# pc_healthypi_pro_carrier_5_2.net
KiCad netlist of a schematic drawn in EAGLE
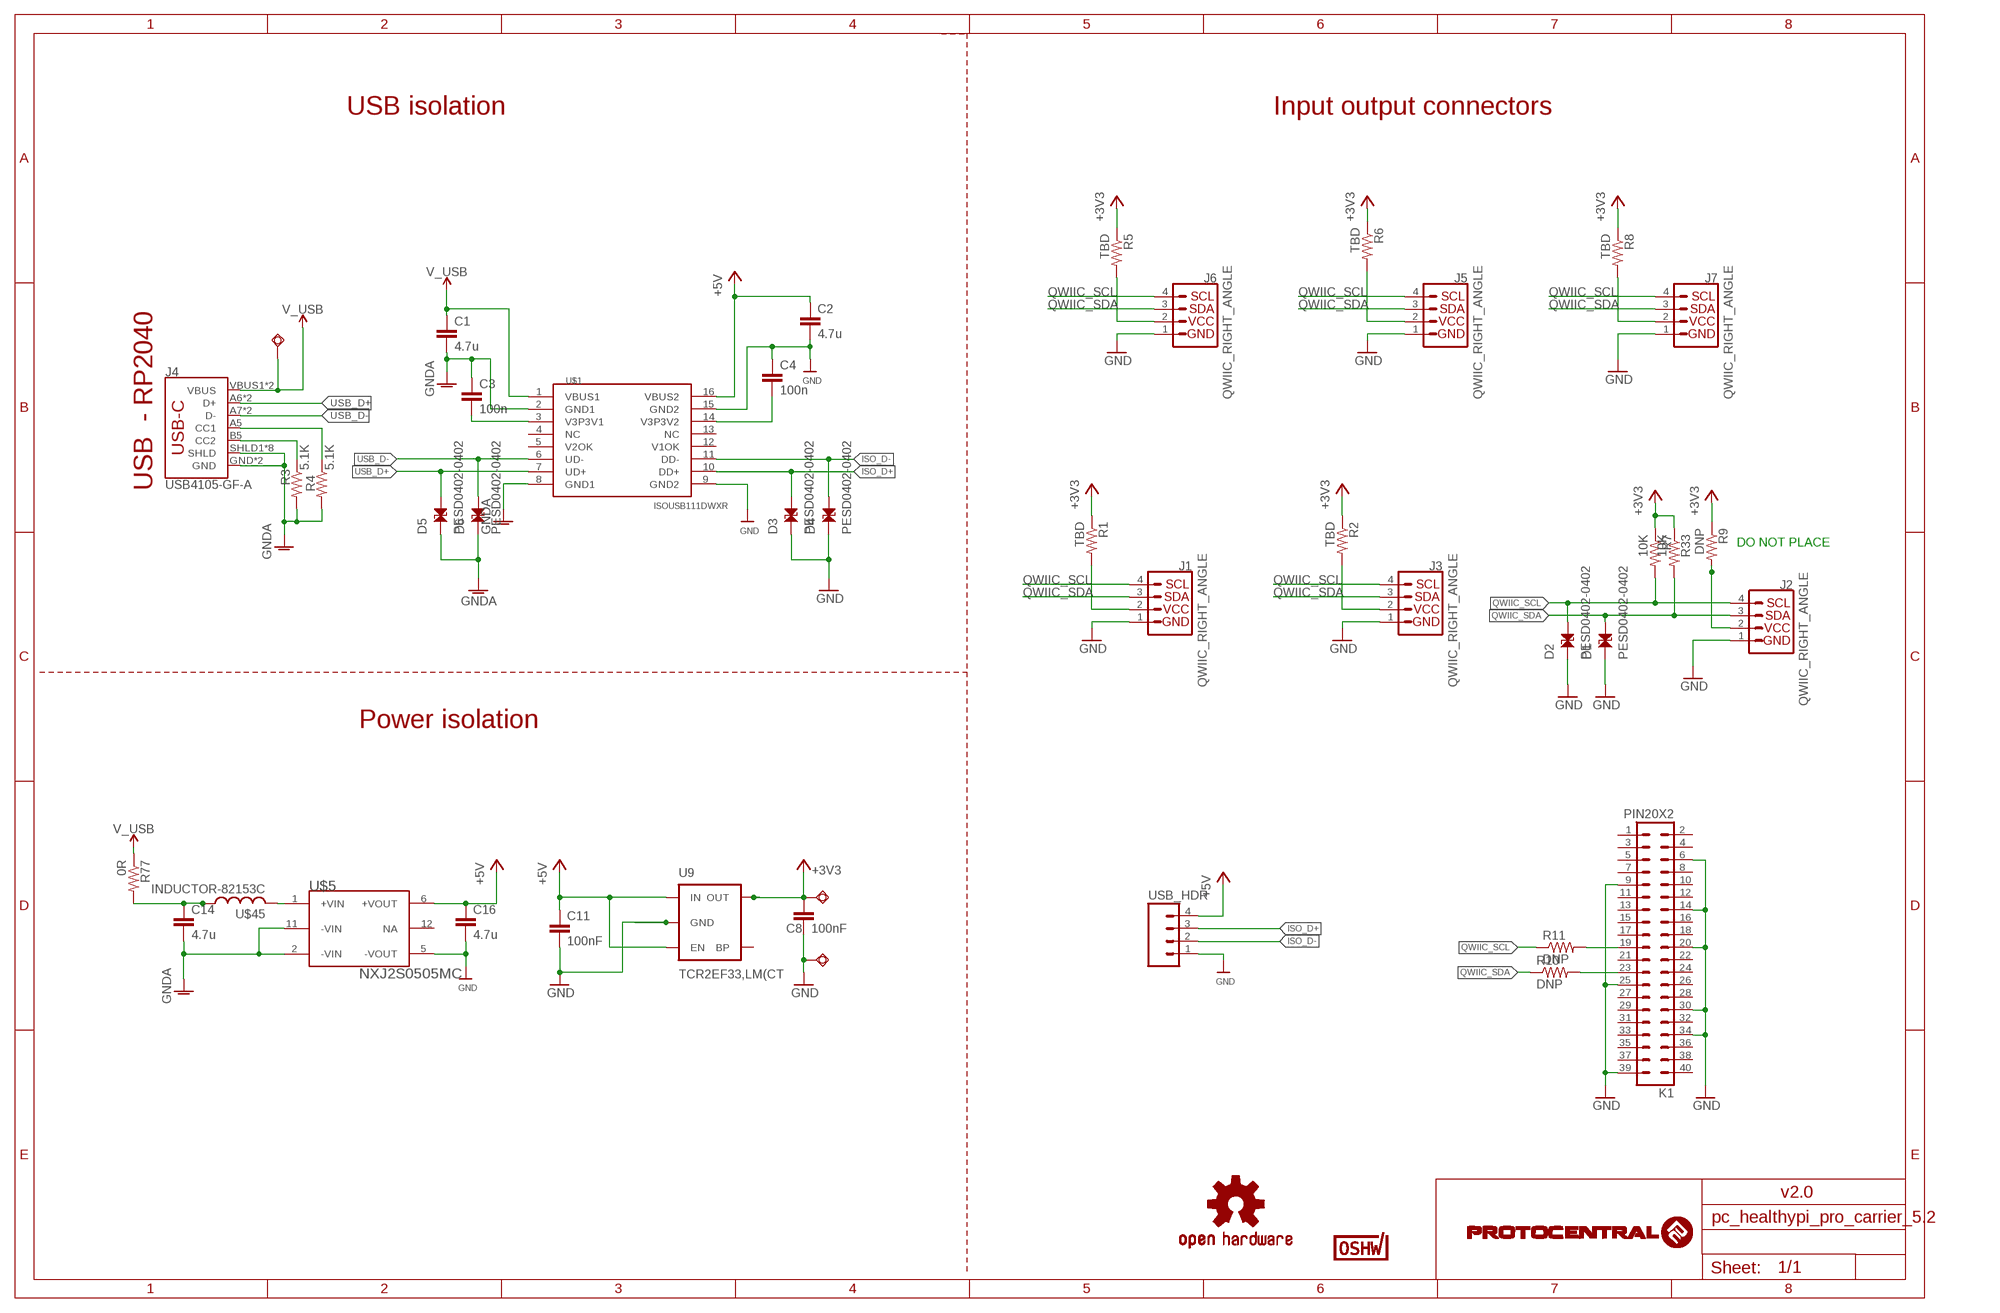
[diagram p0: schematic, sheet 1]

(export (version "E")
  (design (tool "Eeschema 10.0.6"))
  (components
    (comp (ref "C1")
      (value "4.7u")
      (footprint "eagle-import:C0805")
      (libsource (lib "eagle-import") (part "C-EUC0805"))
    )
    (comp (ref "C2")
      (value "4.7u")
      (footprint "eagle-import:C0805")
      (libsource (lib "eagle-import") (part "C-EUC0805"))
    )
    (comp (ref "C3")
      (value "100n")
      (footprint "eagle-import:C0402")
      (libsource (lib "eagle-import") (part "C-EUC0402"))
    )
    (comp (ref "C4")
      (value "100n")
      (footprint "eagle-import:C0402")
      (libsource (lib "eagle-import") (part "C-EUC0402"))
    )
    (comp (ref "C8")
      (value "100nF")
      (footprint "eagle-import:C0402")
      (libsource (lib "eagle-import") (part "C-EUC0402"))
    )
    (comp (ref "C11")
      (value "100nF")
      (footprint "eagle-import:C0402")
      (libsource (lib "eagle-import") (part "C-EUC0402"))
    )
    (comp (ref "C14")
      (value "4.7u")
      (footprint "eagle-import:C0805")
      (libsource (lib "eagle-import") (part "C-EUC0805"))
    )
    (comp (ref "C16")
      (value "4.7u")
      (footprint "eagle-import:C0805")
      (libsource (lib "eagle-import") (part "C-EUC0805"))
    )
    (comp (ref "D1")
      (value "PESD0402-0402")
      (footprint "eagle-import:0402")
      (fields
        (field (name "DIGIKEY_PART") "PESD0402-140CT-ND")
        (field (name "MOUSE_PART") "650-PESD0402-140")
      )
      (libsource (lib "eagle-import") (part "PESD0402-0402"))
    )
    (comp (ref "D2")
      (value "PESD0402-0402")
      (footprint "eagle-import:0402")
      (fields
        (field (name "DIGIKEY_PART") "PESD0402-140CT-ND")
        (field (name "MOUSE_PART") "650-PESD0402-140")
      )
      (libsource (lib "eagle-import") (part "PESD0402-0402"))
    )
    (comp (ref "D3")
      (value "PESD0402-0402")
      (footprint "eagle-import:0402")
      (fields
        (field (name "DIGIKEY_PART") "PESD0402-140CT-ND")
        (field (name "MOUSE_PART") "650-PESD0402-140")
      )
      (libsource (lib "eagle-import") (part "PESD0402-0402"))
    )
    (comp (ref "D4")
      (value "PESD0402-0402")
      (footprint "eagle-import:0402")
      (fields
        (field (name "DIGIKEY_PART") "PESD0402-140CT-ND")
        (field (name "MOUSE_PART") "650-PESD0402-140")
      )
      (libsource (lib "eagle-import") (part "PESD0402-0402"))
    )
    (comp (ref "D5")
      (value "PESD0402-0402")
      (footprint "eagle-import:0402")
      (fields
        (field (name "DIGIKEY_PART") "PESD0402-140CT-ND")
        (field (name "MOUSE_PART") "650-PESD0402-140")
      )
      (libsource (lib "eagle-import") (part "PESD0402-0402"))
    )
    (comp (ref "D6")
      (value "PESD0402-0402")
      (footprint "eagle-import:0402")
      (fields
        (field (name "DIGIKEY_PART") "PESD0402-140CT-ND")
        (field (name "MOUSE_PART") "650-PESD0402-140")
      )
      (libsource (lib "eagle-import") (part "PESD0402-0402"))
    )
    (comp (ref "J1")
      (value "QWIIC_RIGHT_ANGLE")
      (footprint "eagle-import:JST04_1MM_RA")
      (libsource (lib "eagle-import") (part "QWIIC_CONNECTORJS-1MM"))
    )
    (comp (ref "J2")
      (value "QWIIC_RIGHT_ANGLE")
      (footprint "eagle-import:JST04_1MM_RA")
      (libsource (lib "eagle-import") (part "QWIIC_CONNECTORJS-1MM"))
    )
    (comp (ref "J3")
      (value "QWIIC_RIGHT_ANGLE")
      (footprint "eagle-import:JST04_1MM_RA")
      (libsource (lib "eagle-import") (part "QWIIC_CONNECTORJS-1MM"))
    )
    (comp (ref "J4")
      (value "USB4105-GF-A")
      (footprint "eagle-import:USB-C-16P")
      (libsource (lib "eagle-import") (part "USB_C16PIN"))
    )
    (comp (ref "J5")
      (value "QWIIC_RIGHT_ANGLE")
      (footprint "eagle-import:JST04_1MM_RA")
      (libsource (lib "eagle-import") (part "QWIIC_CONNECTORJS-1MM"))
    )
    (comp (ref "J6")
      (value "QWIIC_RIGHT_ANGLE")
      (footprint "eagle-import:JST04_1MM_RA")
      (libsource (lib "eagle-import") (part "QWIIC_CONNECTORJS-1MM"))
    )
    (comp (ref "J7")
      (value "QWIIC_RIGHT_ANGLE")
      (footprint "eagle-import:JST04_1MM_RA")
      (libsource (lib "eagle-import") (part "QWIIC_CONNECTORJS-1MM"))
    )
    (comp (ref "K1")
      (value "PIN20X2")
      (footprint "eagle-import:PIN_20X2")
      (libsource (lib "eagle-import") (part "PIN20X2"))
    )
    (comp (ref "R1")
      (value "TBD")
      (footprint "eagle-import:R0402")
      (libsource (lib "eagle-import") (part "rcl_334_R-US_R0402"))
    )
    (comp (ref "R2")
      (value "TBD")
      (footprint "eagle-import:R0402")
      (libsource (lib "eagle-import") (part "rcl_334_R-US_R0402"))
    )
    (comp (ref "R3")
      (value "5.1K")
      (footprint "eagle-import:R0402")
      (libsource (lib "eagle-import") (part "rcl_334_R-US_R0402"))
    )
    (comp (ref "R4")
      (value "5.1K")
      (footprint "eagle-import:R0402")
      (libsource (lib "eagle-import") (part "rcl_334_R-US_R0402"))
    )
    (comp (ref "R5")
      (value "TBD")
      (footprint "eagle-import:R0402")
      (libsource (lib "eagle-import") (part "rcl_334_R-US_R0402"))
    )
    (comp (ref "R6")
      (value "TBD")
      (footprint "eagle-import:R0402")
      (libsource (lib "eagle-import") (part "rcl_334_R-US_R0402"))
    )
    (comp (ref "R7")
      (value "10K")
      (footprint "eagle-import:R0402")
      (libsource (lib "eagle-import") (part "rcl_334_R-US_R0402"))
    )
    (comp (ref "R8")
      (value "TBD")
      (footprint "eagle-import:R0402")
      (libsource (lib "eagle-import") (part "rcl_334_R-US_R0402"))
    )
    (comp (ref "R9")
      (value "DNP")
      (footprint "eagle-import:R0402")
      (libsource (lib "eagle-import") (part "rcl_334_R-US_R0402"))
    )
    (comp (ref "R10")
      (value "DNP")
      (footprint "eagle-import:R0402")
      (libsource (lib "eagle-import") (part "rcl_334_R-US_R0402"))
    )
    (comp (ref "R11")
      (value "DNP")
      (footprint "eagle-import:R0402")
      (libsource (lib "eagle-import") (part "rcl_334_R-US_R0402"))
    )
    (comp (ref "R33")
      (value "10K")
      (footprint "eagle-import:R0402")
      (libsource (lib "eagle-import") (part "rcl_334_R-US_R0402"))
    )
    (comp (ref "R77")
      (value "0R")
      (footprint "eagle-import:R0805")
      (libsource (lib "eagle-import") (part "R-US_R0805"))
    )
    (comp (ref "SWIO5")
      (value "TPSQTP11R")
      (footprint "eagle-import:TP11R")
      (libsource (lib "eagle-import") (part "TPSQTP11R"))
    )
    (comp (ref "SWIO6")
      (value "TPSQTP11R")
      (footprint "eagle-import:TP11R")
      (libsource (lib "eagle-import") (part "TPSQTP11R"))
    )
    (comp (ref "TP8")
      (value "TPSQTP11R")
      (footprint "eagle-import:TP11R")
      (libsource (lib "eagle-import") (part "TPSQTP11R"))
    )
    (comp (ref "U$1")
      (value "ISOUSB111DWXR")
      (footprint "eagle-import:SSOP-16-5.85X7.5")
      (libsource (lib "eagle-import") (part "ISOUSB111DWXR"))
    )
    (comp (ref "U$5")
      (value "NXJ2S0505MC")
      (footprint "eagle-import:NXJ2S0505MC")
      (libsource (lib "eagle-import") (part "NXJ2S0505MC"))
    )
    (comp (ref "U$13")
      (value "CERT-SMALL")
      (footprint "eagle-import:CERT-SMALL-SILK")
      (libsource (lib "eagle-import") (part "CERT-SMALL"))
    )
    (comp (ref "U$42")
      (value "OSHW-LOGOM")
      (footprint "eagle-import:OSHW-LOGO-M")
      (libsource (lib "eagle-import") (part "OSHW-LOGOM"))
    )
    (comp (ref "U$45")
      (value "INDUCTOR-82153C")
      (footprint "eagle-import:INDUCTOR-8200")
      (libsource (lib "eagle-import") (part "INDUCTOR-82153C"))
    )
    (comp (ref "U9")
      (value "TCR2EF33,LM(CT")
      (footprint "eagle-import:SOT23-5")
      (libsource (lib "eagle-import") (part "V_REG_LDOSMD"))
    )
    (comp (ref "USB_HDR")
      (value "M04LOCK_LONGPADS")
      (footprint "eagle-import:1X04_LOCK_LONGPADS")
      (libsource (lib "eagle-import") (part "M04LOCK_LONGPADS"))
    )
  )
  (nets
    (net (code "1") (name "+3V3") (class "Default")
      (node (ref "C8") (pin "1") (pinfunction "1_1") (pintype "passive"))
      (node (ref "R1") (pin "1") (pinfunction "1_1") (pintype "passive"))
      (node (ref "R2") (pin "1") (pinfunction "1_1") (pintype "passive"))
      (node (ref "R33") (pin "1") (pinfunction "1_1") (pintype "passive"))
      (node (ref "R5") (pin "1") (pinfunction "1_1") (pintype "passive"))
      (node (ref "R6") (pin "1") (pinfunction "1_1") (pintype "passive"))
      (node (ref "R7") (pin "1") (pinfunction "1_1") (pintype "passive"))
      (node (ref "R8") (pin "1") (pinfunction "1_1") (pintype "passive"))
      (node (ref "R9") (pin "1") (pinfunction "1_1") (pintype "passive"))
      (node (ref "SWIO5") (pin "TP") (pinfunction "TP_TP") (pintype "input"))
      (node (ref "U9") (pin "5") (pinfunction "OUT_5") (pintype "passive"))
    )
    (net (code "2") (name "+5V") (class "Default")
      (node (ref "C11") (pin "1") (pinfunction "1_1") (pintype "passive"))
      (node (ref "C16") (pin "1") (pinfunction "1_1") (pintype "passive"))
      (node (ref "C2") (pin "1") (pinfunction "1_1") (pintype "passive"))
      (node (ref "U$1") (pin "16") (pinfunction "VBUS2_16") (pintype "bidirectional"))
      (node (ref "U$5") (pin "6") (pinfunction "+VOUT_6") (pintype "bidirectional"))
      (node (ref "U9") (pin "1") (pinfunction "IN_1") (pintype "input"))
      (node (ref "U9") (pin "3") (pinfunction "EN_3") (pintype "input"))
      (node (ref "USB_HDR") (pin "4") (pinfunction "4_4") (pintype "passive"))
    )
    (net (code "3") (name "GND") (class "Default")
      (node (ref "C11") (pin "2") (pinfunction "2_2") (pintype "passive"))
      (node (ref "C16") (pin "2") (pinfunction "2_2") (pintype "passive"))
      (node (ref "C2") (pin "2") (pinfunction "2_2") (pintype "passive"))
      (node (ref "C4") (pin "1") (pinfunction "1_1") (pintype "passive"))
      (node (ref "C8") (pin "2") (pinfunction "2_2") (pintype "passive"))
      (node (ref "D1") (pin "1") (pinfunction "1_1") (pintype "bidirectional"))
      (node (ref "D2") (pin "1") (pinfunction "1_1") (pintype "bidirectional"))
      (node (ref "D3") (pin "1") (pinfunction "1_1") (pintype "bidirectional"))
      (node (ref "D4") (pin "1") (pinfunction "1_1") (pintype "bidirectional"))
      (node (ref "J1") (pin "1") (pinfunction "1_1") (pintype "power_in"))
      (node (ref "J2") (pin "1") (pinfunction "1_1") (pintype "power_in"))
      (node (ref "J3") (pin "1") (pinfunction "1_1") (pintype "power_in"))
      (node (ref "J5") (pin "1") (pinfunction "1_1") (pintype "power_in"))
      (node (ref "J6") (pin "1") (pinfunction "1_1") (pintype "power_in"))
      (node (ref "J7") (pin "1") (pinfunction "1_1") (pintype "power_in"))
      (node (ref "K1") (pin "14") (pinfunction "14_14") (pintype "passive"))
      (node (ref "K1") (pin "20") (pinfunction "20_20") (pintype "passive"))
      (node (ref "K1") (pin "25") (pinfunction "25_25") (pintype "passive"))
      (node (ref "K1") (pin "30") (pinfunction "30_30") (pintype "passive"))
      (node (ref "K1") (pin "34") (pinfunction "34_34") (pintype "passive"))
      (node (ref "K1") (pin "39") (pinfunction "39_39") (pintype "passive"))
      (node (ref "K1") (pin "6") (pinfunction "6_6") (pintype "passive"))
      (node (ref "K1") (pin "9") (pinfunction "9_9") (pintype "passive"))
      (node (ref "SWIO6") (pin "TP") (pinfunction "TP_TP") (pintype "input"))
      (node (ref "U$1") (pin "15") (pinfunction "GND2_15") (pintype "bidirectional"))
      (node (ref "U$1") (pin "9") (pinfunction "GND2_9") (pintype "bidirectional"))
      (node (ref "U$5") (pin "5") (pinfunction "-VOUT_5") (pintype "bidirectional"))
      (node (ref "U9") (pin "2") (pinfunction "GND_2") (pintype "input"))
      (node (ref "USB_HDR") (pin "1") (pinfunction "1_1") (pintype "passive"))
    )
    (net (code "4") (name "GNDA") (class "Default")
      (node (ref "C1") (pin "2") (pinfunction "2_2") (pintype "passive"))
      (node (ref "C14") (pin "2") (pinfunction "2_2") (pintype "passive"))
      (node (ref "C3") (pin "1") (pinfunction "1_1") (pintype "passive"))
      (node (ref "D5") (pin "1") (pinfunction "1_1") (pintype "bidirectional"))
      (node (ref "D6") (pin "1") (pinfunction "1_1") (pintype "bidirectional"))
      (node (ref "J4") (pin "GND") (pinfunction "GND_GND") (pintype "bidirectional"))
      (node (ref "J4") (pin "GND2") (pinfunction "GND_GND2") (pintype "bidirectional"))
      (node (ref "J4") (pin "SHLD1") (pinfunction "SHLD_SHLD1") (pintype "bidirectional"))
      (node (ref "J4") (pin "SHLD2") (pinfunction "SHLD_SHLD2") (pintype "bidirectional"))
      (node (ref "J4") (pin "SHLD3") (pinfunction "SHLD_SHLD3") (pintype "bidirectional"))
      (node (ref "J4") (pin "SHLD4") (pinfunction "SHLD_SHLD4") (pintype "bidirectional"))
      (node (ref "J4") (pin "SHLD5") (pinfunction "SHLD_SHLD5") (pintype "bidirectional"))
      (node (ref "J4") (pin "SHLD6") (pinfunction "SHLD_SHLD6") (pintype "bidirectional"))
      (node (ref "J4") (pin "SHLD7") (pinfunction "SHLD_SHLD7") (pintype "bidirectional"))
      (node (ref "J4") (pin "SHLD8") (pinfunction "SHLD_SHLD8") (pintype "bidirectional"))
      (node (ref "R3") (pin "2") (pinfunction "2_2") (pintype "passive"))
      (node (ref "R4") (pin "2") (pinfunction "2_2") (pintype "passive"))
      (node (ref "U$1") (pin "2") (pinfunction "GND1_2") (pintype "bidirectional"))
      (node (ref "U$1") (pin "8") (pinfunction "GND1_8") (pintype "bidirectional"))
      (node (ref "U$5") (pin "11") (pinfunction "-VIN_11") (pintype "bidirectional"))
      (node (ref "U$5") (pin "2") (pinfunction "-VIN_2") (pintype "bidirectional"))
    )
    (net (code "5") (name "ISO_D+") (class "Default")
      (node (ref "D3") (pin "2") (pinfunction "2_2") (pintype "bidirectional"))
      (node (ref "U$1") (pin "10") (pinfunction "DD+_10") (pintype "bidirectional"))
      (node (ref "USB_HDR") (pin "3") (pinfunction "3_3") (pintype "passive"))
    )
    (net (code "6") (name "ISO_D-") (class "Default")
      (node (ref "D4") (pin "2") (pinfunction "2_2") (pintype "bidirectional"))
      (node (ref "U$1") (pin "11") (pinfunction "DD-_11") (pintype "bidirectional"))
      (node (ref "USB_HDR") (pin "2") (pinfunction "2_2") (pintype "passive"))
    )
    (net (code "7") (name "Net-(J1-Pad2)") (class "Default")
      (node (ref "J1") (pin "2") (pinfunction "2_2") (pintype "power_in"))
      (node (ref "R1") (pin "2") (pinfunction "2_2") (pintype "passive"))
    )
    (net (code "8") (name "Net-(J2-Pad2)") (class "Default")
      (node (ref "J2") (pin "2") (pinfunction "2_2") (pintype "power_in"))
      (node (ref "R9") (pin "2") (pinfunction "2_2") (pintype "passive"))
    )
    (net (code "9") (name "Net-(J3-Pad2)") (class "Default")
      (node (ref "J3") (pin "2") (pinfunction "2_2") (pintype "power_in"))
      (node (ref "R2") (pin "2") (pinfunction "2_2") (pintype "passive"))
    )
    (net (code "10") (name "Net-(J4-CC1)") (class "Default")
      (node (ref "J4") (pin "A5") (pinfunction "CC1_A5") (pintype "bidirectional"))
      (node (ref "R4") (pin "1") (pinfunction "1_1") (pintype "passive"))
    )
    (net (code "11") (name "Net-(J4-CC2)") (class "Default")
      (node (ref "J4") (pin "B5") (pinfunction "CC2_B5") (pintype "bidirectional"))
      (node (ref "R3") (pin "1") (pinfunction "1_1") (pintype "passive"))
    )
    (net (code "12") (name "Net-(J5-Pad2)") (class "Default")
      (node (ref "J5") (pin "2") (pinfunction "2_2") (pintype "power_in"))
      (node (ref "R6") (pin "2") (pinfunction "2_2") (pintype "passive"))
    )
    (net (code "13") (name "Net-(J6-Pad2)") (class "Default")
      (node (ref "J6") (pin "2") (pinfunction "2_2") (pintype "power_in"))
      (node (ref "R5") (pin "2") (pinfunction "2_2") (pintype "passive"))
    )
    (net (code "14") (name "Net-(J7-Pad2)") (class "Default")
      (node (ref "J7") (pin "2") (pinfunction "2_2") (pintype "power_in"))
      (node (ref "R8") (pin "2") (pinfunction "2_2") (pintype "passive"))
    )
    (net (code "15") (name "Net-(K1-Pad19)") (class "Default")
      (node (ref "K1") (pin "19") (pinfunction "19_19") (pintype "passive"))
      (node (ref "R11") (pin "2") (pinfunction "2_2") (pintype "passive"))
    )
    (net (code "16") (name "Net-(K1-Pad23)") (class "Default")
      (node (ref "K1") (pin "23") (pinfunction "23_23") (pintype "passive"))
      (node (ref "R10") (pin "2") (pinfunction "2_2") (pintype "passive"))
    )
    (net (code "17") (name "Net-(U$1-V3P3V1)") (class "Default")
      (node (ref "C3") (pin "2") (pinfunction "2_2") (pintype "passive"))
      (node (ref "U$1") (pin "3") (pinfunction "V3P3V1_3") (pintype "bidirectional"))
    )
    (net (code "18") (name "Net-(U$1-V3P3V2)") (class "Default")
      (node (ref "C4") (pin "2") (pinfunction "2_2") (pintype "passive"))
      (node (ref "U$1") (pin "14") (pinfunction "V3P3V2_14") (pintype "bidirectional"))
    )
    (net (code "19") (name "Net-(U$45-1)") (class "Default")
      (node (ref "C14") (pin "1") (pinfunction "1_1") (pintype "passive"))
      (node (ref "R77") (pin "2") (pinfunction "2_2") (pintype "passive"))
      (node (ref "U$45") (pin "P$1") (pinfunction "1_P$1") (pintype "passive"))
    )
    (net (code "20") (name "Net-(U$45-2)") (class "Default")
      (node (ref "U$45") (pin "P$2") (pinfunction "2_P$2") (pintype "passive"))
      (node (ref "U$5") (pin "1") (pinfunction "+VIN_1") (pintype "bidirectional"))
    )
    (net (code "21") (name "QWIIC_SCL") (class "Default")
      (node (ref "D2") (pin "2") (pinfunction "2_2") (pintype "bidirectional"))
      (node (ref "J1") (pin "4") (pinfunction "4_4") (pintype "passive"))
      (node (ref "J2") (pin "4") (pinfunction "4_4") (pintype "passive"))
      (node (ref "J3") (pin "4") (pinfunction "4_4") (pintype "passive"))
      (node (ref "J5") (pin "4") (pinfunction "4_4") (pintype "passive"))
      (node (ref "J6") (pin "4") (pinfunction "4_4") (pintype "passive"))
      (node (ref "J7") (pin "4") (pinfunction "4_4") (pintype "passive"))
      (node (ref "R11") (pin "1") (pinfunction "1_1") (pintype "passive"))
      (node (ref "R7") (pin "2") (pinfunction "2_2") (pintype "passive"))
    )
    (net (code "22") (name "QWIIC_SDA") (class "Default")
      (node (ref "D1") (pin "2") (pinfunction "2_2") (pintype "bidirectional"))
      (node (ref "J1") (pin "3") (pinfunction "3_3") (pintype "passive"))
      (node (ref "J2") (pin "3") (pinfunction "3_3") (pintype "passive"))
      (node (ref "J3") (pin "3") (pinfunction "3_3") (pintype "passive"))
      (node (ref "J5") (pin "3") (pinfunction "3_3") (pintype "passive"))
      (node (ref "J6") (pin "3") (pinfunction "3_3") (pintype "passive"))
      (node (ref "J7") (pin "3") (pinfunction "3_3") (pintype "passive"))
      (node (ref "R10") (pin "1") (pinfunction "1_1") (pintype "passive"))
      (node (ref "R33") (pin "2") (pinfunction "2_2") (pintype "passive"))
    )
    (net (code "23") (name "USB_D+") (class "Default")
      (node (ref "D5") (pin "2") (pinfunction "2_2") (pintype "bidirectional"))
      (node (ref "J4") (pin "A6") (pinfunction "D+_A6") (pintype "bidirectional"))
      (node (ref "J4") (pin "B6") (pinfunction "D+_B6") (pintype "bidirectional"))
      (node (ref "U$1") (pin "7") (pinfunction "UD+_7") (pintype "bidirectional"))
    )
    (net (code "24") (name "USB_D-") (class "Default")
      (node (ref "D6") (pin "2") (pinfunction "2_2") (pintype "bidirectional"))
      (node (ref "J4") (pin "A7") (pinfunction "D-_A7") (pintype "bidirectional"))
      (node (ref "J4") (pin "B7") (pinfunction "D-_B7") (pintype "bidirectional"))
      (node (ref "U$1") (pin "6") (pinfunction "UD-_6") (pintype "bidirectional"))
    )
    (net (code "25") (name "V_USB") (class "Default")
      (node (ref "C1") (pin "1") (pinfunction "1_1") (pintype "passive"))
      (node (ref "J4") (pin "VBUS1") (pinfunction "VBUS_VBUS1") (pintype "bidirectional"))
      (node (ref "J4") (pin "VBUS2") (pinfunction "VBUS_VBUS2") (pintype "bidirectional"))
      (node (ref "R77") (pin "1") (pinfunction "1_1") (pintype "passive"))
      (node (ref "TP8") (pin "TP") (pinfunction "TP_TP") (pintype "input"))
      (node (ref "U$1") (pin "1") (pinfunction "VBUS1_1") (pintype "bidirectional"))
    )
    (net (code "26") (name "unconnected-(K1-Pad1)") (class "Default")
      (node (ref "K1") (pin "1") (pinfunction "1_1") (pintype "passive"))
    )
    (net (code "27") (name "unconnected-(K1-Pad2)") (class "Default")
      (node (ref "K1") (pin "2") (pinfunction "2_2") (pintype "passive"))
    )
    (net (code "28") (name "unconnected-(K1-Pad3)") (class "Default")
      (node (ref "K1") (pin "3") (pinfunction "3_3") (pintype "passive"))
    )
    (net (code "29") (name "unconnected-(K1-Pad4)") (class "Default")
      (node (ref "K1") (pin "4") (pinfunction "4_4") (pintype "passive"))
    )
    (net (code "30") (name "unconnected-(K1-Pad5)") (class "Default")
      (node (ref "K1") (pin "5") (pinfunction "5_5") (pintype "passive"))
    )
    (net (code "31") (name "unconnected-(K1-Pad7)") (class "Default")
      (node (ref "K1") (pin "7") (pinfunction "7_7") (pintype "passive"))
    )
    (net (code "32") (name "unconnected-(K1-Pad8)") (class "Default")
      (node (ref "K1") (pin "8") (pinfunction "8_8") (pintype "passive"))
    )
    (net (code "33") (name "unconnected-(K1-Pad10)") (class "Default")
      (node (ref "K1") (pin "10") (pinfunction "10_10") (pintype "passive"))
    )
    (net (code "34") (name "unconnected-(K1-Pad11)") (class "Default")
      (node (ref "K1") (pin "11") (pinfunction "11_11") (pintype "passive"))
    )
    (net (code "35") (name "unconnected-(K1-Pad12)") (class "Default")
      (node (ref "K1") (pin "12") (pinfunction "12_12") (pintype "passive"))
    )
    (net (code "36") (name "unconnected-(K1-Pad13)") (class "Default")
      (node (ref "K1") (pin "13") (pinfunction "13_13") (pintype "passive"))
    )
    (net (code "37") (name "unconnected-(K1-Pad15)") (class "Default")
      (node (ref "K1") (pin "15") (pinfunction "15_15") (pintype "passive"))
    )
    (net (code "38") (name "unconnected-(K1-Pad16)") (class "Default")
      (node (ref "K1") (pin "16") (pinfunction "16_16") (pintype "passive"))
    )
    (net (code "39") (name "unconnected-(K1-Pad17)") (class "Default")
      (node (ref "K1") (pin "17") (pinfunction "17_17") (pintype "passive"))
    )
    (net (code "40") (name "unconnected-(K1-Pad18)") (class "Default")
      (node (ref "K1") (pin "18") (pinfunction "18_18") (pintype "passive"))
    )
    (net (code "41") (name "unconnected-(K1-Pad21)") (class "Default")
      (node (ref "K1") (pin "21") (pinfunction "21_21") (pintype "passive"))
    )
    (net (code "42") (name "unconnected-(K1-Pad22)") (class "Default")
      (node (ref "K1") (pin "22") (pinfunction "22_22") (pintype "passive"))
    )
    (net (code "43") (name "unconnected-(K1-Pad24)") (class "Default")
      (node (ref "K1") (pin "24") (pinfunction "24_24") (pintype "passive"))
    )
    (net (code "44") (name "unconnected-(K1-Pad26)") (class "Default")
      (node (ref "K1") (pin "26") (pinfunction "26_26") (pintype "passive"))
    )
    (net (code "45") (name "unconnected-(K1-Pad27)") (class "Default")
      (node (ref "K1") (pin "27") (pinfunction "27_27") (pintype "passive"))
    )
    (net (code "46") (name "unconnected-(K1-Pad28)") (class "Default")
      (node (ref "K1") (pin "28") (pinfunction "28_28") (pintype "passive"))
    )
    (net (code "47") (name "unconnected-(K1-Pad29)") (class "Default")
      (node (ref "K1") (pin "29") (pinfunction "29_29") (pintype "passive"))
    )
    (net (code "48") (name "unconnected-(K1-Pad31)") (class "Default")
      (node (ref "K1") (pin "31") (pinfunction "31_31") (pintype "passive"))
    )
    (net (code "49") (name "unconnected-(K1-Pad32)") (class "Default")
      (node (ref "K1") (pin "32") (pinfunction "32_32") (pintype "passive"))
    )
    (net (code "50") (name "unconnected-(K1-Pad33)") (class "Default")
      (node (ref "K1") (pin "33") (pinfunction "33_33") (pintype "passive"))
    )
    (net (code "51") (name "unconnected-(K1-Pad35)") (class "Default")
      (node (ref "K1") (pin "35") (pinfunction "35_35") (pintype "passive"))
    )
    (net (code "52") (name "unconnected-(K1-Pad36)") (class "Default")
      (node (ref "K1") (pin "36") (pinfunction "36_36") (pintype "passive"))
    )
    (net (code "53") (name "unconnected-(K1-Pad37)") (class "Default")
      (node (ref "K1") (pin "37") (pinfunction "37_37") (pintype "passive"))
    )
    (net (code "54") (name "unconnected-(K1-Pad38)") (class "Default")
      (node (ref "K1") (pin "38") (pinfunction "38_38") (pintype "passive"))
    )
    (net (code "55") (name "unconnected-(K1-Pad40)") (class "Default")
      (node (ref "K1") (pin "40") (pinfunction "40_40") (pintype "passive"))
    )
    (net (code "56") (name "unconnected-(U$1-NC-Pad4)") (class "Default")
      (node (ref "U$1") (pin "4") (pinfunction "NC_4") (pintype "bidirectional"))
    )
    (net (code "57") (name "unconnected-(U$1-NC-Pad13)") (class "Default")
      (node (ref "U$1") (pin "13") (pinfunction "NC_13") (pintype "bidirectional"))
    )
    (net (code "58") (name "unconnected-(U$1-V1OK-Pad12)") (class "Default")
      (node (ref "U$1") (pin "12") (pinfunction "V1OK_12") (pintype "bidirectional"))
    )
    (net (code "59") (name "unconnected-(U$1-V2OK-Pad5)") (class "Default")
      (node (ref "U$1") (pin "5") (pinfunction "V2OK_5") (pintype "bidirectional"))
    )
    (net (code "60") (name "unconnected-(U$5-NA-Pad12)") (class "Default")
      (node (ref "U$5") (pin "12") (pinfunction "NA_12") (pintype "bidirectional"))
    )
    (net (code "61") (name "unconnected-(U9-BP-Pad4)") (class "Default")
      (node (ref "U9") (pin "4") (pinfunction "BP_4") (pintype "input"))
    )
  )
)
